# av_amp_04.net
KiCad netlist of a schematic drawn in EAGLE
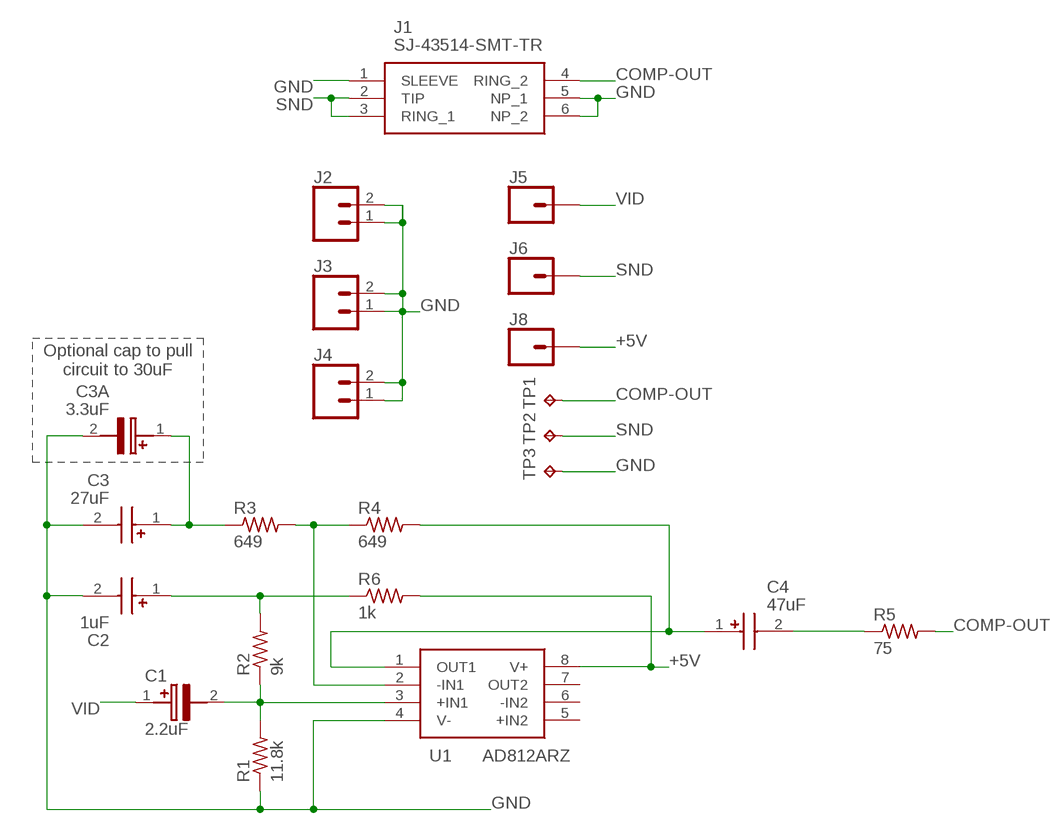
[diagram p0: schematic, sheet 1]

(export (version "E")
  (design (tool "Eeschema 10.0.6"))
  (components
    (comp (ref "C1")
      (value "2.2uF")
      (footprint "eagle-import:CAPAE430X550N")
      (fields
        (field (name "MANUFACTURER_PART_NUMBER") "EEE-FC1H2R2R")
        (field (name "MOUSER_PART_NUMBER") "667-EEE-FC1H2R2R")
      )
      (libsource (lib "eagle-import") (part "EEE-FC1H2R2R"))
    )
    (comp (ref "C2")
      (value "1uF")
      (footprint "eagle-import:CAPAE430X565N")
      (fields
        (field (name "MANUFACTURER_PART_NUMBER") "EDH105M050S9BAA")
        (field (name "MOUSER_PART_NUMBER") "80-EDH105M050S9BAA")
      )
      (libsource (lib "eagle-import") (part "EDH105M050S9BAA"))
    )
    (comp (ref "C3")
      (value "27uF")
      (footprint "eagle-import:865080342004")
      (fields
        (field (name "MANUFACTURER_PART_NUMBER") "865080342004")
        (field (name "MOUSER_PART_NUMBER") "710-865080342004")
      )
      (libsource (lib "eagle-import") (part "865080342004"))
    )
    (comp (ref "C3A")
      (value "3.3uF")
      (footprint "eagle-import:865080540001")
      (fields
        (field (name "MANUFACTURER_PART_NUMBER") "865080540001")
        (field (name "MOUSER_PART_NUMBER") "710-865080540001")
      )
      (libsource (lib "eagle-import") (part "865080540001"))
    )
    (comp (ref "C4")
      (value "47uF")
      (footprint "eagle-import:EDK(5X5.4)")
      (fields
        (field (name "MANUFACTURER_PART_NUMBER") "EDK476M016A9DAA")
        (field (name "MOUSER_PART_NUMBER") "80-EDK476M016A9DAA")
      )
      (libsource (lib "eagle-import") (part "EDK476M016A9DAA"))
    )
    (comp (ref "J1")
      (value "SJ-43514-SMT-TR")
      (footprint "eagle-import:SJ-43514-SMT-TR")
      (fields (field (name "MOUSER_PART_NUMBER") "490-SJ-43514-SMT-TR"))
      (libsource (lib "eagle-import") (part "SJ-43514-SMT-TR"))
    )
    (comp (ref "J2")
      (value "CONN_02")
      (footprint "eagle-import:1X02")
      (libsource (lib "eagle-import") (part "CONN_02"))
    )
    (comp (ref "J3")
      (value "CONN_02")
      (footprint "eagle-import:1X02")
      (libsource (lib "eagle-import") (part "CONN_02"))
    )
    (comp (ref "J4")
      (value "CONN_02")
      (footprint "eagle-import:1X02")
      (libsource (lib "eagle-import") (part "CONN_02"))
    )
    (comp (ref "J5")
      (value "CONN_01")
      (footprint "eagle-import:1X01")
      (libsource (lib "eagle-import") (part "CONN_01"))
    )
    (comp (ref "J6")
      (value "CONN_01")
      (footprint "eagle-import:1X01")
      (libsource (lib "eagle-import") (part "CONN_01"))
    )
    (comp (ref "J8")
      (value "CONN_01")
      (footprint "eagle-import:1X01")
      (libsource (lib "eagle-import") (part "CONN_01"))
    )
    (comp (ref "R1")
      (value "11.8k")
      (footprint "eagle-import:R0603")
      (libsource (lib "eagle-import") (part "R-US_R0603"))
    )
    (comp (ref "R2")
      (value "9k")
      (footprint "eagle-import:R0603")
      (libsource (lib "eagle-import") (part "R-US_R0603"))
    )
    (comp (ref "R3")
      (value "649")
      (footprint "eagle-import:R0603")
      (libsource (lib "eagle-import") (part "R-US_R0603"))
    )
    (comp (ref "R4")
      (value "649")
      (footprint "eagle-import:R0603")
      (libsource (lib "eagle-import") (part "R-US_R0603"))
    )
    (comp (ref "R5")
      (value "75")
      (footprint "eagle-import:R0603")
      (libsource (lib "eagle-import") (part "R-US_R0603"))
    )
    (comp (ref "R6")
      (value "1k")
      (footprint "eagle-import:R0603")
      (libsource (lib "eagle-import") (part "R-US_R0603"))
    )
    (comp (ref "TP1")
      (value "TPB2,54")
      (footprint "eagle-import:B2,54")
      (libsource (lib "eagle-import") (part "TPB2,54"))
    )
    (comp (ref "TP2")
      (value "TPB2,54")
      (footprint "eagle-import:B2,54")
      (libsource (lib "eagle-import") (part "TPB2,54"))
    )
    (comp (ref "TP3")
      (value "TPB2,54")
      (footprint "eagle-import:B2,54")
      (libsource (lib "eagle-import") (part "TPB2,54"))
    )
    (comp (ref "U1")
      (value "AD812ARZ")
      (footprint "eagle-import:SOIC127P600X175-8N")
      (fields (field (name "MOUSER_PART_NUMBER") "584-AD812ARZ"))
      (libsource (lib "eagle-import") (part "AD812ARZ"))
    )
  )
  (nets
    (net (code "1") (name "/+5V") (class "Default")
      (node (ref "J8") (pin "1") (pinfunction "1_1") (pintype "passive"))
      (node (ref "R6") (pin "2") (pinfunction "2_2") (pintype "passive"))
      (node (ref "U1") (pin "8") (pinfunction "V+_8") (pintype "bidirectional"))
    )
    (net (code "2") (name "/COMP-OUT") (class "Default")
      (node (ref "J1") (pin "4") (pinfunction "RING_2_4") (pintype "bidirectional"))
      (node (ref "R5") (pin "2") (pinfunction "2_2") (pintype "passive"))
      (node (ref "TP1") (pin "TP") (pinfunction "TP_TP") (pintype "input"))
    )
    (net (code "3") (name "/GND") (class "Default")
      (node (ref "C2") (pin "2") (pinfunction "-_2") (pintype "bidirectional"))
      (node (ref "C3") (pin "2") (pinfunction "+_2") (pintype "bidirectional"))
      (node (ref "C3A") (pin "2") (pinfunction "-_2") (pintype "bidirectional"))
      (node (ref "J1") (pin "1") (pinfunction "SLEEVE_1") (pintype "bidirectional"))
      (node (ref "J1") (pin "5") (pinfunction "NP_1_5") (pintype "bidirectional"))
      (node (ref "J1") (pin "6") (pinfunction "NP_2_6") (pintype "bidirectional"))
      (node (ref "J2") (pin "1") (pinfunction "1_1") (pintype "passive"))
      (node (ref "J2") (pin "2") (pinfunction "2_2") (pintype "passive"))
      (node (ref "J3") (pin "1") (pinfunction "1_1") (pintype "passive"))
      (node (ref "J3") (pin "2") (pinfunction "2_2") (pintype "passive"))
      (node (ref "J4") (pin "1") (pinfunction "1_1") (pintype "passive"))
      (node (ref "J4") (pin "2") (pinfunction "2_2") (pintype "passive"))
      (node (ref "R1") (pin "1") (pinfunction "1_1") (pintype "passive"))
      (node (ref "TP3") (pin "TP") (pinfunction "TP_TP") (pintype "input"))
      (node (ref "U1") (pin "4") (pinfunction "V-_4") (pintype "bidirectional"))
    )
    (net (code "4") (name "/SND") (class "Default")
      (node (ref "J1") (pin "2") (pinfunction "TIP_2") (pintype "bidirectional"))
      (node (ref "J1") (pin "3") (pinfunction "RING_1_3") (pintype "bidirectional"))
      (node (ref "J6") (pin "1") (pinfunction "1_1") (pintype "passive"))
      (node (ref "TP2") (pin "TP") (pinfunction "TP_TP") (pintype "input"))
    )
    (net (code "5") (name "/VID") (class "Default")
      (node (ref "C1") (pin "1") (pinfunction "+_1") (pintype "bidirectional"))
      (node (ref "J5") (pin "1") (pinfunction "1_1") (pintype "passive"))
    )
    (net (code "6") (name "Net-(C1--)") (class "Default")
      (node (ref "C1") (pin "2") (pinfunction "-_2") (pintype "bidirectional"))
      (node (ref "R1") (pin "2") (pinfunction "2_2") (pintype "passive"))
      (node (ref "R2") (pin "1") (pinfunction "1_1") (pintype "passive"))
      (node (ref "U1") (pin "3") (pinfunction "+IN1_3") (pintype "input"))
    )
    (net (code "7") (name "Net-(C2-+)") (class "Default")
      (node (ref "C2") (pin "1") (pinfunction "+_1") (pintype "bidirectional"))
      (node (ref "R2") (pin "2") (pinfunction "2_2") (pintype "passive"))
      (node (ref "R6") (pin "1") (pinfunction "1_1") (pintype "passive"))
    )
    (net (code "8") (name "Net-(C3--)") (class "Default")
      (node (ref "C3") (pin "1") (pinfunction "-_1") (pintype "bidirectional"))
      (node (ref "C3A") (pin "1") (pinfunction "+_1") (pintype "bidirectional"))
      (node (ref "R3") (pin "1") (pinfunction "1_1") (pintype "passive"))
    )
    (net (code "9") (name "Net-(C4-+)") (class "Default")
      (node (ref "C4") (pin "1") (pinfunction "+_1") (pintype "bidirectional"))
      (node (ref "R4") (pin "2") (pinfunction "2_2") (pintype "passive"))
      (node (ref "U1") (pin "1") (pinfunction "OUT1_1") (pintype "output"))
    )
    (net (code "10") (name "Net-(C4--)") (class "Default")
      (node (ref "C4") (pin "2") (pinfunction "-_2") (pintype "bidirectional"))
      (node (ref "R5") (pin "1") (pinfunction "1_1") (pintype "passive"))
    )
    (net (code "11") (name "Net-(U1--IN1)") (class "Default")
      (node (ref "R3") (pin "2") (pinfunction "2_2") (pintype "passive"))
      (node (ref "R4") (pin "1") (pinfunction "1_1") (pintype "passive"))
      (node (ref "U1") (pin "2") (pinfunction "-IN1_2") (pintype "input"))
    )
    (net (code "12") (name "unconnected-(U1-+IN2-Pad5)") (class "Default")
      (node (ref "U1") (pin "5") (pinfunction "+IN2_5") (pintype "input"))
    )
    (net (code "13") (name "unconnected-(U1--IN2-Pad6)") (class "Default")
      (node (ref "U1") (pin "6") (pinfunction "-IN2_6") (pintype "input"))
    )
    (net (code "14") (name "unconnected-(U1-OUT2-Pad7)") (class "Default")
      (node (ref "U1") (pin "7") (pinfunction "OUT2_7") (pintype "output"))
    )
  )
)
